# NucciL.net
KiCad netlist of a schematic drawn in Altium Designer
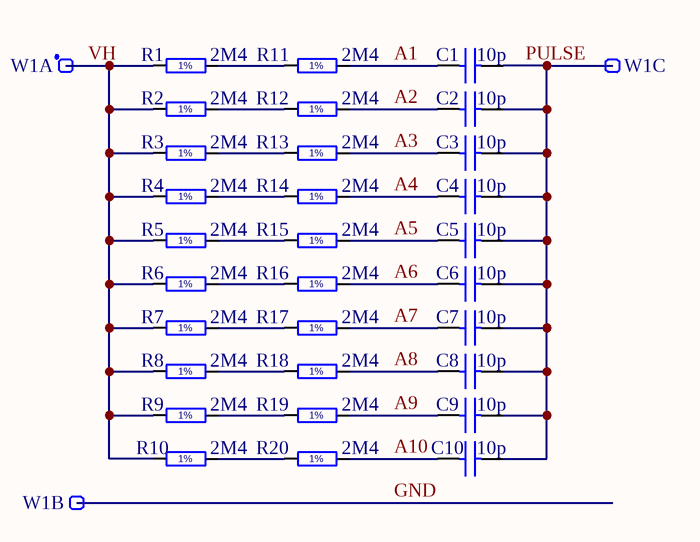
[diagram p0: NucciL.SchDoc]

(export (version "E")
  (design (tool "Eeschema 10.0.6"))
  (components
    (comp (ref "C1")
      (value "10p")
      (footprint "CAPC3216X70N")
      (description "Non-polarised capacitor")
      (fields
        (field (name "PART NUMBER") "CC1206_10PF_500V_5%_NP0")
        (field (name "VOLTAGE") "500V")
        (field (name "AUTHOR") "CERN DEM JLC")
      )
      (libsource (lib "Capacitors") (part "Capacitor - non polarized"))
    )
    (comp (ref "C2")
      (value "10p")
      (footprint "CAPC3216X70N")
      (description "Non-polarised capacitor")
      (fields
        (field (name "PART NUMBER") "CC1206_10PF_500V_5%_NP0")
        (field (name "VOLTAGE") "500V")
        (field (name "AUTHOR") "CERN DEM JLC")
      )
      (libsource (lib "Capacitors") (part "Capacitor - non polarized"))
    )
    (comp (ref "C3")
      (value "10p")
      (footprint "CAPC3216X70N")
      (description "Non-polarised capacitor")
      (fields
        (field (name "PART NUMBER") "CC1206_10PF_500V_5%_NP0")
        (field (name "VOLTAGE") "500V")
        (field (name "AUTHOR") "CERN DEM JLC")
      )
      (libsource (lib "Capacitors") (part "Capacitor - non polarized"))
    )
    (comp (ref "C4")
      (value "10p")
      (footprint "CAPC3216X70N")
      (description "Non-polarised capacitor")
      (fields
        (field (name "PART NUMBER") "CC1206_10PF_500V_5%_NP0")
        (field (name "VOLTAGE") "500V")
        (field (name "AUTHOR") "CERN DEM JLC")
      )
      (libsource (lib "Capacitors") (part "Capacitor - non polarized"))
    )
    (comp (ref "C5")
      (value "10p")
      (footprint "CAPC3216X70N")
      (description "Non-polarised capacitor")
      (fields
        (field (name "PART NUMBER") "CC1206_10PF_500V_5%_NP0")
        (field (name "VOLTAGE") "500V")
        (field (name "AUTHOR") "CERN DEM JLC")
      )
      (libsource (lib "Capacitors") (part "Capacitor - non polarized"))
    )
    (comp (ref "C6")
      (value "10p")
      (footprint "CAPC3216X70N")
      (description "Non-polarised capacitor")
      (fields
        (field (name "PART NUMBER") "CC1206_10PF_500V_5%_NP0")
        (field (name "VOLTAGE") "500V")
        (field (name "AUTHOR") "CERN DEM JLC")
      )
      (libsource (lib "Capacitors") (part "Capacitor - non polarized"))
    )
    (comp (ref "C7")
      (value "10p")
      (footprint "CAPC3216X70N")
      (description "Non-polarised capacitor")
      (fields
        (field (name "PART NUMBER") "CC1206_10PF_500V_5%_NP0")
        (field (name "VOLTAGE") "500V")
        (field (name "AUTHOR") "CERN DEM JLC")
      )
      (libsource (lib "Capacitors") (part "Capacitor - non polarized"))
    )
    (comp (ref "C8")
      (value "10p")
      (footprint "CAPC3216X70N")
      (description "Non-polarised capacitor")
      (fields
        (field (name "PART NUMBER") "CC1206_10PF_500V_5%_NP0")
        (field (name "VOLTAGE") "500V")
        (field (name "AUTHOR") "CERN DEM JLC")
      )
      (libsource (lib "Capacitors") (part "Capacitor - non polarized"))
    )
    (comp (ref "C9")
      (value "10p")
      (footprint "CAPC3216X70N")
      (description "Non-polarised capacitor")
      (fields
        (field (name "PART NUMBER") "CC1206_10PF_500V_5%_NP0")
        (field (name "VOLTAGE") "500V")
        (field (name "AUTHOR") "CERN DEM JLC")
      )
      (libsource (lib "Capacitors") (part "Capacitor - non polarized"))
    )
    (comp (ref "C10")
      (value "10p")
      (footprint "CAPC3216X70N")
      (description "Non-polarised capacitor")
      (fields
        (field (name "PART NUMBER") "CC1206_10PF_500V_5%_NP0")
        (field (name "VOLTAGE") "500V")
        (field (name "AUTHOR") "CERN DEM JLC")
      )
      (libsource (lib "Capacitors") (part "Capacitor - non polarized"))
    )
    (comp (ref "R1")
      (value "2M4")
      (footprint "RESC3216X65N")
      (description "Resistor - 1%")
      (fields
        (field (name "PART NUMBER") "R1206_2M4_1%_0.25W_100PPM")
        (field (name "POWER") "0.25W")
        (field (name "AUTHOR") "DEL")
      )
      (libsource (lib "Resistors") (part "Resistor - 1%"))
    )
    (comp (ref "R2")
      (value "2M4")
      (footprint "RESC3216X65N")
      (description "Resistor - 1%")
      (fields
        (field (name "PART NUMBER") "R1206_2M4_1%_0.25W_100PPM")
        (field (name "POWER") "0.25W")
        (field (name "AUTHOR") "DEL")
      )
      (libsource (lib "Resistors") (part "Resistor - 1%"))
    )
    (comp (ref "R3")
      (value "2M4")
      (footprint "RESC3216X65N")
      (description "Resistor - 1%")
      (fields
        (field (name "PART NUMBER") "R1206_2M4_1%_0.25W_100PPM")
        (field (name "POWER") "0.25W")
        (field (name "AUTHOR") "DEL")
      )
      (libsource (lib "Resistors") (part "Resistor - 1%"))
    )
    (comp (ref "R4")
      (value "2M4")
      (footprint "RESC3216X65N")
      (description "Resistor - 1%")
      (fields
        (field (name "PART NUMBER") "R1206_2M4_1%_0.25W_100PPM")
        (field (name "POWER") "0.25W")
        (field (name "AUTHOR") "DEL")
      )
      (libsource (lib "Resistors") (part "Resistor - 1%"))
    )
    (comp (ref "R5")
      (value "2M4")
      (footprint "RESC3216X65N")
      (description "Resistor - 1%")
      (fields
        (field (name "PART NUMBER") "R1206_2M4_1%_0.25W_100PPM")
        (field (name "POWER") "0.25W")
        (field (name "AUTHOR") "DEL")
      )
      (libsource (lib "Resistors") (part "Resistor - 1%"))
    )
    (comp (ref "R6")
      (value "2M4")
      (footprint "RESC3216X65N")
      (description "Resistor - 1%")
      (fields
        (field (name "PART NUMBER") "R1206_2M4_1%_0.25W_100PPM")
        (field (name "POWER") "0.25W")
        (field (name "AUTHOR") "DEL")
      )
      (libsource (lib "Resistors") (part "Resistor - 1%"))
    )
    (comp (ref "R7")
      (value "2M4")
      (footprint "RESC3216X65N")
      (description "Resistor - 1%")
      (fields
        (field (name "PART NUMBER") "R1206_2M4_1%_0.25W_100PPM")
        (field (name "POWER") "0.25W")
        (field (name "AUTHOR") "DEL")
      )
      (libsource (lib "Resistors") (part "Resistor - 1%"))
    )
    (comp (ref "R8")
      (value "2M4")
      (footprint "RESC3216X65N")
      (description "Resistor - 1%")
      (fields
        (field (name "PART NUMBER") "R1206_2M4_1%_0.25W_100PPM")
        (field (name "POWER") "0.25W")
        (field (name "AUTHOR") "DEL")
      )
      (libsource (lib "Resistors") (part "Resistor - 1%"))
    )
    (comp (ref "R9")
      (value "2M4")
      (footprint "RESC3216X65N")
      (description "Resistor - 1%")
      (fields
        (field (name "PART NUMBER") "R1206_2M4_1%_0.25W_100PPM")
        (field (name "POWER") "0.25W")
        (field (name "AUTHOR") "DEL")
      )
      (libsource (lib "Resistors") (part "Resistor - 1%"))
    )
    (comp (ref "R10")
      (value "2M4")
      (footprint "RESC3216X65N")
      (description "Resistor - 1%")
      (fields
        (field (name "PART NUMBER") "R1206_2M4_1%_0.25W_100PPM")
        (field (name "POWER") "0.25W")
        (field (name "AUTHOR") "DEL")
      )
      (libsource (lib "Resistors") (part "Resistor - 1%"))
    )
    (comp (ref "R11")
      (value "2M4")
      (footprint "RESC3216X65N")
      (description "Resistor - 1%")
      (fields
        (field (name "PART NUMBER") "R1206_2M4_1%_0.25W_100PPM")
        (field (name "POWER") "0.25W")
        (field (name "AUTHOR") "DEL")
      )
      (libsource (lib "Resistors") (part "Resistor - 1%"))
    )
    (comp (ref "R12")
      (value "2M4")
      (footprint "RESC3216X65N")
      (description "Resistor - 1%")
      (fields
        (field (name "PART NUMBER") "R1206_2M4_1%_0.25W_100PPM")
        (field (name "POWER") "0.25W")
        (field (name "AUTHOR") "DEL")
      )
      (libsource (lib "Resistors") (part "Resistor - 1%"))
    )
    (comp (ref "R13")
      (value "2M4")
      (footprint "RESC3216X65N")
      (description "Resistor - 1%")
      (fields
        (field (name "PART NUMBER") "R1206_2M4_1%_0.25W_100PPM")
        (field (name "POWER") "0.25W")
        (field (name "AUTHOR") "DEL")
      )
      (libsource (lib "Resistors") (part "Resistor - 1%"))
    )
    (comp (ref "R14")
      (value "2M4")
      (footprint "RESC3216X65N")
      (description "Resistor - 1%")
      (fields
        (field (name "PART NUMBER") "R1206_2M4_1%_0.25W_100PPM")
        (field (name "POWER") "0.25W")
        (field (name "AUTHOR") "DEL")
      )
      (libsource (lib "Resistors") (part "Resistor - 1%"))
    )
    (comp (ref "R15")
      (value "2M4")
      (footprint "RESC3216X65N")
      (description "Resistor - 1%")
      (fields
        (field (name "PART NUMBER") "R1206_2M4_1%_0.25W_100PPM")
        (field (name "POWER") "0.25W")
        (field (name "AUTHOR") "DEL")
      )
      (libsource (lib "Resistors") (part "Resistor - 1%"))
    )
    (comp (ref "R16")
      (value "2M4")
      (footprint "RESC3216X65N")
      (description "Resistor - 1%")
      (fields
        (field (name "PART NUMBER") "R1206_2M4_1%_0.25W_100PPM")
        (field (name "POWER") "0.25W")
        (field (name "AUTHOR") "DEL")
      )
      (libsource (lib "Resistors") (part "Resistor - 1%"))
    )
    (comp (ref "R17")
      (value "2M4")
      (footprint "RESC3216X65N")
      (description "Resistor - 1%")
      (fields
        (field (name "PART NUMBER") "R1206_2M4_1%_0.25W_100PPM")
        (field (name "POWER") "0.25W")
        (field (name "AUTHOR") "DEL")
      )
      (libsource (lib "Resistors") (part "Resistor - 1%"))
    )
    (comp (ref "R18")
      (value "2M4")
      (footprint "RESC3216X65N")
      (description "Resistor - 1%")
      (fields
        (field (name "PART NUMBER") "R1206_2M4_1%_0.25W_100PPM")
        (field (name "POWER") "0.25W")
        (field (name "AUTHOR") "DEL")
      )
      (libsource (lib "Resistors") (part "Resistor - 1%"))
    )
    (comp (ref "R19")
      (value "2M4")
      (footprint "RESC3216X65N")
      (description "Resistor - 1%")
      (fields
        (field (name "PART NUMBER") "R1206_2M4_1%_0.25W_100PPM")
        (field (name "POWER") "0.25W")
        (field (name "AUTHOR") "DEL")
      )
      (libsource (lib "Resistors") (part "Resistor - 1%"))
    )
    (comp (ref "R20")
      (value "2M4")
      (footprint "RESC3216X65N")
      (description "Resistor - 1%")
      (fields
        (field (name "PART NUMBER") "R1206_2M4_1%_0.25W_100PPM")
        (field (name "POWER") "0.25W")
        (field (name "AUTHOR") "DEL")
      )
      (libsource (lib "Resistors") (part "Resistor - 1%"))
    )
    (comp (ref "W1")
      (value "Test Point")
      (footprint "COMATEL_385.0358.1.03.400")
      (description "3 Mini Wire-Wrap Contact Strip Header")
      (fields
        (field (name "PART NUMBER") "COMATEL_385.0358.1.03.400")
        (field (name "MANUFACTURER") "KONTEK COMATEL")
        (field (name "AUTHOR") "CERN DEM JLC")
      )
      (libsource (lib "Connectors") (part "Wire-Wrap Contact x3"))
    )
  )
  (nets
    (net (code "1") (name "/A1") (class "Default")
      (node (ref "C1") (pin "1") (pinfunction "1_1") (pintype "passive"))
      (node (ref "R11") (pin "2") (pinfunction "2_2") (pintype "passive"))
    )
    (net (code "2") (name "/A2") (class "Default")
      (node (ref "C2") (pin "1") (pinfunction "1_1") (pintype "passive"))
      (node (ref "R12") (pin "2") (pinfunction "2_2") (pintype "passive"))
    )
    (net (code "3") (name "/A3") (class "Default")
      (node (ref "C3") (pin "1") (pinfunction "1_1") (pintype "passive"))
      (node (ref "R13") (pin "2") (pinfunction "2_2") (pintype "passive"))
    )
    (net (code "4") (name "/A4") (class "Default")
      (node (ref "C4") (pin "1") (pinfunction "1_1") (pintype "passive"))
      (node (ref "R14") (pin "2") (pinfunction "2_2") (pintype "passive"))
    )
    (net (code "5") (name "/A5") (class "Default")
      (node (ref "C5") (pin "1") (pinfunction "1_1") (pintype "passive"))
      (node (ref "R15") (pin "2") (pinfunction "2_2") (pintype "passive"))
    )
    (net (code "6") (name "/A6") (class "Default")
      (node (ref "C6") (pin "1") (pinfunction "1_1") (pintype "passive"))
      (node (ref "R16") (pin "2") (pinfunction "2_2") (pintype "passive"))
    )
    (net (code "7") (name "/A7") (class "Default")
      (node (ref "C7") (pin "1") (pinfunction "1_1") (pintype "passive"))
      (node (ref "R17") (pin "2") (pinfunction "2_2") (pintype "passive"))
    )
    (net (code "8") (name "/A8") (class "Default")
      (node (ref "C8") (pin "1") (pinfunction "1_1") (pintype "passive"))
      (node (ref "R18") (pin "2") (pinfunction "2_2") (pintype "passive"))
    )
    (net (code "9") (name "/A9") (class "Default")
      (node (ref "C9") (pin "1") (pinfunction "1_1") (pintype "passive"))
      (node (ref "R19") (pin "2") (pinfunction "2_2") (pintype "passive"))
    )
    (net (code "10") (name "/A10") (class "Default")
      (node (ref "C10") (pin "1") (pinfunction "1_1") (pintype "passive"))
      (node (ref "R20") (pin "2") (pinfunction "2_2") (pintype "passive"))
    )
    (net (code "11") (name "/GND") (class "Default")
      (node (ref "W1") (pin "2") (pinfunction "2_2") (pintype "bidirectional"))
    )
    (net (code "12") (name "/PULSE") (class "Default")
      (node (ref "C1") (pin "2") (pinfunction "2_2") (pintype "passive"))
      (node (ref "C10") (pin "2") (pinfunction "2_2") (pintype "passive"))
      (node (ref "C2") (pin "2") (pinfunction "2_2") (pintype "passive"))
      (node (ref "C3") (pin "2") (pinfunction "2_2") (pintype "passive"))
      (node (ref "C4") (pin "2") (pinfunction "2_2") (pintype "passive"))
      (node (ref "C5") (pin "2") (pinfunction "2_2") (pintype "passive"))
      (node (ref "C6") (pin "2") (pinfunction "2_2") (pintype "passive"))
      (node (ref "C7") (pin "2") (pinfunction "2_2") (pintype "passive"))
      (node (ref "C8") (pin "2") (pinfunction "2_2") (pintype "passive"))
      (node (ref "C9") (pin "2") (pinfunction "2_2") (pintype "passive"))
      (node (ref "W1") (pin "3") (pinfunction "3_3") (pintype "bidirectional"))
    )
    (net (code "13") (name "/VH") (class "Default")
      (node (ref "R1") (pin "1") (pinfunction "1_1") (pintype "passive"))
      (node (ref "R10") (pin "1") (pinfunction "1_1") (pintype "passive"))
      (node (ref "R2") (pin "1") (pinfunction "1_1") (pintype "passive"))
      (node (ref "R3") (pin "1") (pinfunction "1_1") (pintype "passive"))
      (node (ref "R4") (pin "1") (pinfunction "1_1") (pintype "passive"))
      (node (ref "R5") (pin "1") (pinfunction "1_1") (pintype "passive"))
      (node (ref "R6") (pin "1") (pinfunction "1_1") (pintype "passive"))
      (node (ref "R7") (pin "1") (pinfunction "1_1") (pintype "passive"))
      (node (ref "R8") (pin "1") (pinfunction "1_1") (pintype "passive"))
      (node (ref "R9") (pin "1") (pinfunction "1_1") (pintype "passive"))
      (node (ref "W1") (pin "1") (pinfunction "1_1") (pintype "bidirectional"))
    )
    (net (code "14") (name "Net-(R1-Pad2)") (class "Default")
      (node (ref "R1") (pin "2") (pinfunction "2_2") (pintype "passive"))
      (node (ref "R11") (pin "1") (pinfunction "1_1") (pintype "passive"))
    )
    (net (code "15") (name "Net-(R10-Pad2)") (class "Default")
      (node (ref "R10") (pin "2") (pinfunction "2_2") (pintype "passive"))
      (node (ref "R20") (pin "1") (pinfunction "1_1") (pintype "passive"))
    )
    (net (code "16") (name "Net-(R12-Pad1)") (class "Default")
      (node (ref "R12") (pin "1") (pinfunction "1_1") (pintype "passive"))
      (node (ref "R2") (pin "2") (pinfunction "2_2") (pintype "passive"))
    )
    (net (code "17") (name "Net-(R13-Pad1)") (class "Default")
      (node (ref "R13") (pin "1") (pinfunction "1_1") (pintype "passive"))
      (node (ref "R3") (pin "2") (pinfunction "2_2") (pintype "passive"))
    )
    (net (code "18") (name "Net-(R14-Pad1)") (class "Default")
      (node (ref "R14") (pin "1") (pinfunction "1_1") (pintype "passive"))
      (node (ref "R4") (pin "2") (pinfunction "2_2") (pintype "passive"))
    )
    (net (code "19") (name "Net-(R15-Pad1)") (class "Default")
      (node (ref "R15") (pin "1") (pinfunction "1_1") (pintype "passive"))
      (node (ref "R5") (pin "2") (pinfunction "2_2") (pintype "passive"))
    )
    (net (code "20") (name "Net-(R16-Pad1)") (class "Default")
      (node (ref "R16") (pin "1") (pinfunction "1_1") (pintype "passive"))
      (node (ref "R6") (pin "2") (pinfunction "2_2") (pintype "passive"))
    )
    (net (code "21") (name "Net-(R17-Pad1)") (class "Default")
      (node (ref "R17") (pin "1") (pinfunction "1_1") (pintype "passive"))
      (node (ref "R7") (pin "2") (pinfunction "2_2") (pintype "passive"))
    )
    (net (code "22") (name "Net-(R18-Pad1)") (class "Default")
      (node (ref "R18") (pin "1") (pinfunction "1_1") (pintype "passive"))
      (node (ref "R8") (pin "2") (pinfunction "2_2") (pintype "passive"))
    )
    (net (code "23") (name "Net-(R19-Pad1)") (class "Default")
      (node (ref "R19") (pin "1") (pinfunction "1_1") (pintype "passive"))
      (node (ref "R9") (pin "2") (pinfunction "2_2") (pintype "passive"))
    )
  )
)
